# FFChkMate.net
KiCad netlist of a schematic drawn in EAGLE
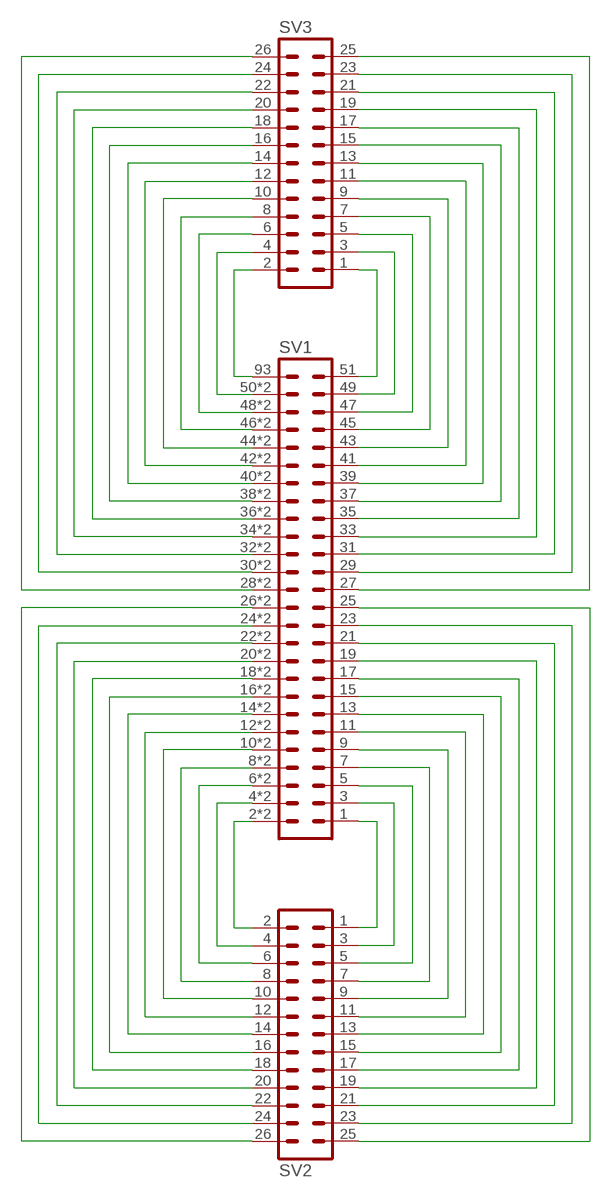
[diagram p0: schematic, sheet 1]

(export (version "E")
  (design (tool "Eeschema 10.0.6"))
  (components
    (comp (ref "SV1")
      (value "03MM")
      (footprint "eagle-import:03MM")
      (libsource (lib "eagle-import") (part "03MM"))
    )
    (comp (ref "SV2")
      (value "MA13-2")
      (footprint "eagle-import:MA13-2")
      (libsource (lib "eagle-import") (part "MA13-2"))
    )
    (comp (ref "SV3")
      (value "MA13-2")
      (footprint "eagle-import:MA13-2")
      (libsource (lib "eagle-import") (part "MA13-2"))
    )
  )
  (nets
    (net (code "1") (name "Net-(SV1-2-Pad68)") (class "Default")
      (node (ref "SV1") (pin "2") (pinfunction "2_2") (pintype "passive"))
      (node (ref "SV1") (pin "68") (pinfunction "2_68") (pintype "passive"))
      (node (ref "SV2") (pin "2") (pinfunction "2_2") (pintype "passive"))
    )
    (net (code "2") (name "Net-(SV1-4-Pad69)") (class "Default")
      (node (ref "SV1") (pin "4") (pinfunction "4_4") (pintype "passive"))
      (node (ref "SV1") (pin "69") (pinfunction "4_69") (pintype "passive"))
      (node (ref "SV2") (pin "4") (pinfunction "4_4") (pintype "passive"))
    )
    (net (code "3") (name "Net-(SV1-6-Pad70)") (class "Default")
      (node (ref "SV1") (pin "6") (pinfunction "6_6") (pintype "passive"))
      (node (ref "SV1") (pin "70") (pinfunction "6_70") (pintype "passive"))
      (node (ref "SV2") (pin "6") (pinfunction "6_6") (pintype "passive"))
    )
    (net (code "4") (name "Net-(SV1-8-Pad71)") (class "Default")
      (node (ref "SV1") (pin "71") (pinfunction "8_71") (pintype "passive"))
      (node (ref "SV1") (pin "8") (pinfunction "8_8") (pintype "passive"))
      (node (ref "SV2") (pin "8") (pinfunction "8_8") (pintype "passive"))
    )
    (net (code "5") (name "Net-(SV1-10-Pad72)") (class "Default")
      (node (ref "SV1") (pin "10") (pinfunction "10_10") (pintype "passive"))
      (node (ref "SV1") (pin "72") (pinfunction "10_72") (pintype "passive"))
      (node (ref "SV2") (pin "10") (pinfunction "10_10") (pintype "passive"))
    )
    (net (code "6") (name "Net-(SV1-12-Pad73)") (class "Default")
      (node (ref "SV1") (pin "12") (pinfunction "12_12") (pintype "passive"))
      (node (ref "SV1") (pin "73") (pinfunction "12_73") (pintype "passive"))
      (node (ref "SV2") (pin "12") (pinfunction "12_12") (pintype "passive"))
    )
    (net (code "7") (name "Net-(SV1-14-Pad74)") (class "Default")
      (node (ref "SV1") (pin "14") (pinfunction "14_14") (pintype "passive"))
      (node (ref "SV1") (pin "74") (pinfunction "14_74") (pintype "passive"))
      (node (ref "SV2") (pin "14") (pinfunction "14_14") (pintype "passive"))
    )
    (net (code "8") (name "Net-(SV1-16-Pad75)") (class "Default")
      (node (ref "SV1") (pin "16") (pinfunction "16_16") (pintype "passive"))
      (node (ref "SV1") (pin "75") (pinfunction "16_75") (pintype "passive"))
      (node (ref "SV2") (pin "16") (pinfunction "16_16") (pintype "passive"))
    )
    (net (code "9") (name "Net-(SV1-18-Pad76)") (class "Default")
      (node (ref "SV1") (pin "18") (pinfunction "18_18") (pintype "passive"))
      (node (ref "SV1") (pin "76") (pinfunction "18_76") (pintype "passive"))
      (node (ref "SV2") (pin "18") (pinfunction "18_18") (pintype "passive"))
    )
    (net (code "10") (name "Net-(SV1-20-Pad77)") (class "Default")
      (node (ref "SV1") (pin "20") (pinfunction "20_20") (pintype "passive"))
      (node (ref "SV1") (pin "77") (pinfunction "20_77") (pintype "passive"))
      (node (ref "SV2") (pin "20") (pinfunction "20_20") (pintype "passive"))
    )
    (net (code "11") (name "Net-(SV1-22-Pad78)") (class "Default")
      (node (ref "SV1") (pin "22") (pinfunction "22_22") (pintype "passive"))
      (node (ref "SV1") (pin "78") (pinfunction "22_78") (pintype "passive"))
      (node (ref "SV2") (pin "22") (pinfunction "22_22") (pintype "passive"))
    )
    (net (code "12") (name "Net-(SV1-24-Pad79)") (class "Default")
      (node (ref "SV1") (pin "24") (pinfunction "24_24") (pintype "passive"))
      (node (ref "SV1") (pin "79") (pinfunction "24_79") (pintype "passive"))
      (node (ref "SV2") (pin "24") (pinfunction "24_24") (pintype "passive"))
    )
    (net (code "13") (name "Net-(SV1-26-Pad80)") (class "Default")
      (node (ref "SV1") (pin "26") (pinfunction "26_26") (pintype "passive"))
      (node (ref "SV1") (pin "80") (pinfunction "26_80") (pintype "passive"))
      (node (ref "SV2") (pin "26") (pinfunction "26_26") (pintype "passive"))
    )
    (net (code "14") (name "Net-(SV1-28-Pad81)") (class "Default")
      (node (ref "SV1") (pin "28") (pinfunction "28_28") (pintype "passive"))
      (node (ref "SV1") (pin "81") (pinfunction "28_81") (pintype "passive"))
      (node (ref "SV3") (pin "26") (pinfunction "26_26") (pintype "passive"))
    )
    (net (code "15") (name "Net-(SV1-30-Pad82)") (class "Default")
      (node (ref "SV1") (pin "30") (pinfunction "30_30") (pintype "passive"))
      (node (ref "SV1") (pin "82") (pinfunction "30_82") (pintype "passive"))
      (node (ref "SV3") (pin "24") (pinfunction "24_24") (pintype "passive"))
    )
    (net (code "16") (name "Net-(SV1-32-Pad83)") (class "Default")
      (node (ref "SV1") (pin "32") (pinfunction "32_32") (pintype "passive"))
      (node (ref "SV1") (pin "83") (pinfunction "32_83") (pintype "passive"))
      (node (ref "SV3") (pin "22") (pinfunction "22_22") (pintype "passive"))
    )
    (net (code "17") (name "Net-(SV1-34-Pad84)") (class "Default")
      (node (ref "SV1") (pin "34") (pinfunction "34_34") (pintype "passive"))
      (node (ref "SV1") (pin "84") (pinfunction "34_84") (pintype "passive"))
      (node (ref "SV3") (pin "20") (pinfunction "20_20") (pintype "passive"))
    )
    (net (code "18") (name "Net-(SV1-36-Pad85)") (class "Default")
      (node (ref "SV1") (pin "36") (pinfunction "36_36") (pintype "passive"))
      (node (ref "SV1") (pin "85") (pinfunction "36_85") (pintype "passive"))
      (node (ref "SV3") (pin "18") (pinfunction "18_18") (pintype "passive"))
    )
    (net (code "19") (name "Net-(SV1-38-Pad86)") (class "Default")
      (node (ref "SV1") (pin "38") (pinfunction "38_38") (pintype "passive"))
      (node (ref "SV1") (pin "86") (pinfunction "38_86") (pintype "passive"))
      (node (ref "SV3") (pin "16") (pinfunction "16_16") (pintype "passive"))
    )
    (net (code "20") (name "Net-(SV1-40-Pad87)") (class "Default")
      (node (ref "SV1") (pin "40") (pinfunction "40_40") (pintype "passive"))
      (node (ref "SV1") (pin "87") (pinfunction "40_87") (pintype "passive"))
      (node (ref "SV3") (pin "14") (pinfunction "14_14") (pintype "passive"))
    )
    (net (code "21") (name "Net-(SV1-42-Pad88)") (class "Default")
      (node (ref "SV1") (pin "42") (pinfunction "42_42") (pintype "passive"))
      (node (ref "SV1") (pin "88") (pinfunction "42_88") (pintype "passive"))
      (node (ref "SV3") (pin "12") (pinfunction "12_12") (pintype "passive"))
    )
    (net (code "22") (name "Net-(SV1-44-Pad89)") (class "Default")
      (node (ref "SV1") (pin "44") (pinfunction "44_44") (pintype "passive"))
      (node (ref "SV1") (pin "89") (pinfunction "44_89") (pintype "passive"))
      (node (ref "SV3") (pin "10") (pinfunction "10_10") (pintype "passive"))
    )
    (net (code "23") (name "Net-(SV1-46-Pad90)") (class "Default")
      (node (ref "SV1") (pin "46") (pinfunction "46_46") (pintype "passive"))
      (node (ref "SV1") (pin "90") (pinfunction "46_90") (pintype "passive"))
      (node (ref "SV3") (pin "8") (pinfunction "8_8") (pintype "passive"))
    )
    (net (code "24") (name "Net-(SV1-48-Pad91)") (class "Default")
      (node (ref "SV1") (pin "48") (pinfunction "48_48") (pintype "passive"))
      (node (ref "SV1") (pin "91") (pinfunction "48_91") (pintype "passive"))
      (node (ref "SV3") (pin "6") (pinfunction "6_6") (pintype "passive"))
    )
    (net (code "25") (name "Net-(SV1-50-Pad92)") (class "Default")
      (node (ref "SV1") (pin "50") (pinfunction "50_50") (pintype "passive"))
      (node (ref "SV1") (pin "92") (pinfunction "50_92") (pintype "passive"))
      (node (ref "SV3") (pin "4") (pinfunction "4_4") (pintype "passive"))
    )
    (net (code "26") (name "Net-(SV1-52)") (class "Default")
      (node (ref "SV1") (pin "93") (pinfunction "52_93") (pintype "passive"))
      (node (ref "SV3") (pin "2") (pinfunction "2_2") (pintype "passive"))
    )
    (net (code "27") (name "Net-(SV1-Pad1)") (class "Default")
      (node (ref "SV1") (pin "1") (pinfunction "1_1") (pintype "passive"))
      (node (ref "SV2") (pin "1") (pinfunction "1_1") (pintype "passive"))
    )
    (net (code "28") (name "Net-(SV1-Pad3)") (class "Default")
      (node (ref "SV1") (pin "3") (pinfunction "3_3") (pintype "passive"))
      (node (ref "SV2") (pin "3") (pinfunction "3_3") (pintype "passive"))
    )
    (net (code "29") (name "Net-(SV1-Pad5)") (class "Default")
      (node (ref "SV1") (pin "5") (pinfunction "5_5") (pintype "passive"))
      (node (ref "SV2") (pin "5") (pinfunction "5_5") (pintype "passive"))
    )
    (net (code "30") (name "Net-(SV1-Pad7)") (class "Default")
      (node (ref "SV1") (pin "7") (pinfunction "7_7") (pintype "passive"))
      (node (ref "SV2") (pin "7") (pinfunction "7_7") (pintype "passive"))
    )
    (net (code "31") (name "Net-(SV1-Pad9)") (class "Default")
      (node (ref "SV1") (pin "9") (pinfunction "9_9") (pintype "passive"))
      (node (ref "SV2") (pin "9") (pinfunction "9_9") (pintype "passive"))
    )
    (net (code "32") (name "Net-(SV1-Pad11)") (class "Default")
      (node (ref "SV1") (pin "11") (pinfunction "11_11") (pintype "passive"))
      (node (ref "SV2") (pin "11") (pinfunction "11_11") (pintype "passive"))
    )
    (net (code "33") (name "Net-(SV1-Pad13)") (class "Default")
      (node (ref "SV1") (pin "13") (pinfunction "13_13") (pintype "passive"))
      (node (ref "SV2") (pin "13") (pinfunction "13_13") (pintype "passive"))
    )
    (net (code "34") (name "Net-(SV1-Pad15)") (class "Default")
      (node (ref "SV1") (pin "15") (pinfunction "15_15") (pintype "passive"))
      (node (ref "SV2") (pin "15") (pinfunction "15_15") (pintype "passive"))
    )
    (net (code "35") (name "Net-(SV1-Pad17)") (class "Default")
      (node (ref "SV1") (pin "17") (pinfunction "17_17") (pintype "passive"))
      (node (ref "SV2") (pin "17") (pinfunction "17_17") (pintype "passive"))
    )
    (net (code "36") (name "Net-(SV1-Pad19)") (class "Default")
      (node (ref "SV1") (pin "19") (pinfunction "19_19") (pintype "passive"))
      (node (ref "SV2") (pin "19") (pinfunction "19_19") (pintype "passive"))
    )
    (net (code "37") (name "Net-(SV1-Pad21)") (class "Default")
      (node (ref "SV1") (pin "21") (pinfunction "21_21") (pintype "passive"))
      (node (ref "SV2") (pin "21") (pinfunction "21_21") (pintype "passive"))
    )
    (net (code "38") (name "Net-(SV1-Pad23)") (class "Default")
      (node (ref "SV1") (pin "23") (pinfunction "23_23") (pintype "passive"))
      (node (ref "SV2") (pin "23") (pinfunction "23_23") (pintype "passive"))
    )
    (net (code "39") (name "Net-(SV1-Pad25)") (class "Default")
      (node (ref "SV1") (pin "25") (pinfunction "25_25") (pintype "passive"))
      (node (ref "SV2") (pin "25") (pinfunction "25_25") (pintype "passive"))
    )
    (net (code "40") (name "Net-(SV1-Pad27)") (class "Default")
      (node (ref "SV1") (pin "27") (pinfunction "27_27") (pintype "passive"))
      (node (ref "SV3") (pin "25") (pinfunction "25_25") (pintype "passive"))
    )
    (net (code "41") (name "Net-(SV1-Pad29)") (class "Default")
      (node (ref "SV1") (pin "29") (pinfunction "29_29") (pintype "passive"))
      (node (ref "SV3") (pin "23") (pinfunction "23_23") (pintype "passive"))
    )
    (net (code "42") (name "Net-(SV1-Pad31)") (class "Default")
      (node (ref "SV1") (pin "31") (pinfunction "31_31") (pintype "passive"))
      (node (ref "SV3") (pin "21") (pinfunction "21_21") (pintype "passive"))
    )
    (net (code "43") (name "Net-(SV1-Pad33)") (class "Default")
      (node (ref "SV1") (pin "33") (pinfunction "33_33") (pintype "passive"))
      (node (ref "SV3") (pin "19") (pinfunction "19_19") (pintype "passive"))
    )
    (net (code "44") (name "Net-(SV1-Pad35)") (class "Default")
      (node (ref "SV1") (pin "35") (pinfunction "35_35") (pintype "passive"))
      (node (ref "SV3") (pin "17") (pinfunction "17_17") (pintype "passive"))
    )
    (net (code "45") (name "Net-(SV1-Pad37)") (class "Default")
      (node (ref "SV1") (pin "37") (pinfunction "37_37") (pintype "passive"))
      (node (ref "SV3") (pin "15") (pinfunction "15_15") (pintype "passive"))
    )
    (net (code "46") (name "Net-(SV1-Pad39)") (class "Default")
      (node (ref "SV1") (pin "39") (pinfunction "39_39") (pintype "passive"))
      (node (ref "SV3") (pin "13") (pinfunction "13_13") (pintype "passive"))
    )
    (net (code "47") (name "Net-(SV1-Pad41)") (class "Default")
      (node (ref "SV1") (pin "41") (pinfunction "41_41") (pintype "passive"))
      (node (ref "SV3") (pin "11") (pinfunction "11_11") (pintype "passive"))
    )
    (net (code "48") (name "Net-(SV1-Pad43)") (class "Default")
      (node (ref "SV1") (pin "43") (pinfunction "43_43") (pintype "passive"))
      (node (ref "SV3") (pin "9") (pinfunction "9_9") (pintype "passive"))
    )
    (net (code "49") (name "Net-(SV1-Pad45)") (class "Default")
      (node (ref "SV1") (pin "45") (pinfunction "45_45") (pintype "passive"))
      (node (ref "SV3") (pin "7") (pinfunction "7_7") (pintype "passive"))
    )
    (net (code "50") (name "Net-(SV1-Pad47)") (class "Default")
      (node (ref "SV1") (pin "47") (pinfunction "47_47") (pintype "passive"))
      (node (ref "SV3") (pin "5") (pinfunction "5_5") (pintype "passive"))
    )
    (net (code "51") (name "Net-(SV1-Pad49)") (class "Default")
      (node (ref "SV1") (pin "49") (pinfunction "49_49") (pintype "passive"))
      (node (ref "SV3") (pin "3") (pinfunction "3_3") (pintype "passive"))
    )
    (net (code "52") (name "Net-(SV1-Pad51)") (class "Default")
      (node (ref "SV1") (pin "51") (pinfunction "51_51") (pintype "passive"))
      (node (ref "SV3") (pin "1") (pinfunction "1_1") (pintype "passive"))
    )
  )
)
